# MySen_raspiGateway_EasyEDA_Schematic.net
KiCad netlist of a schematic drawn in EasyEDA
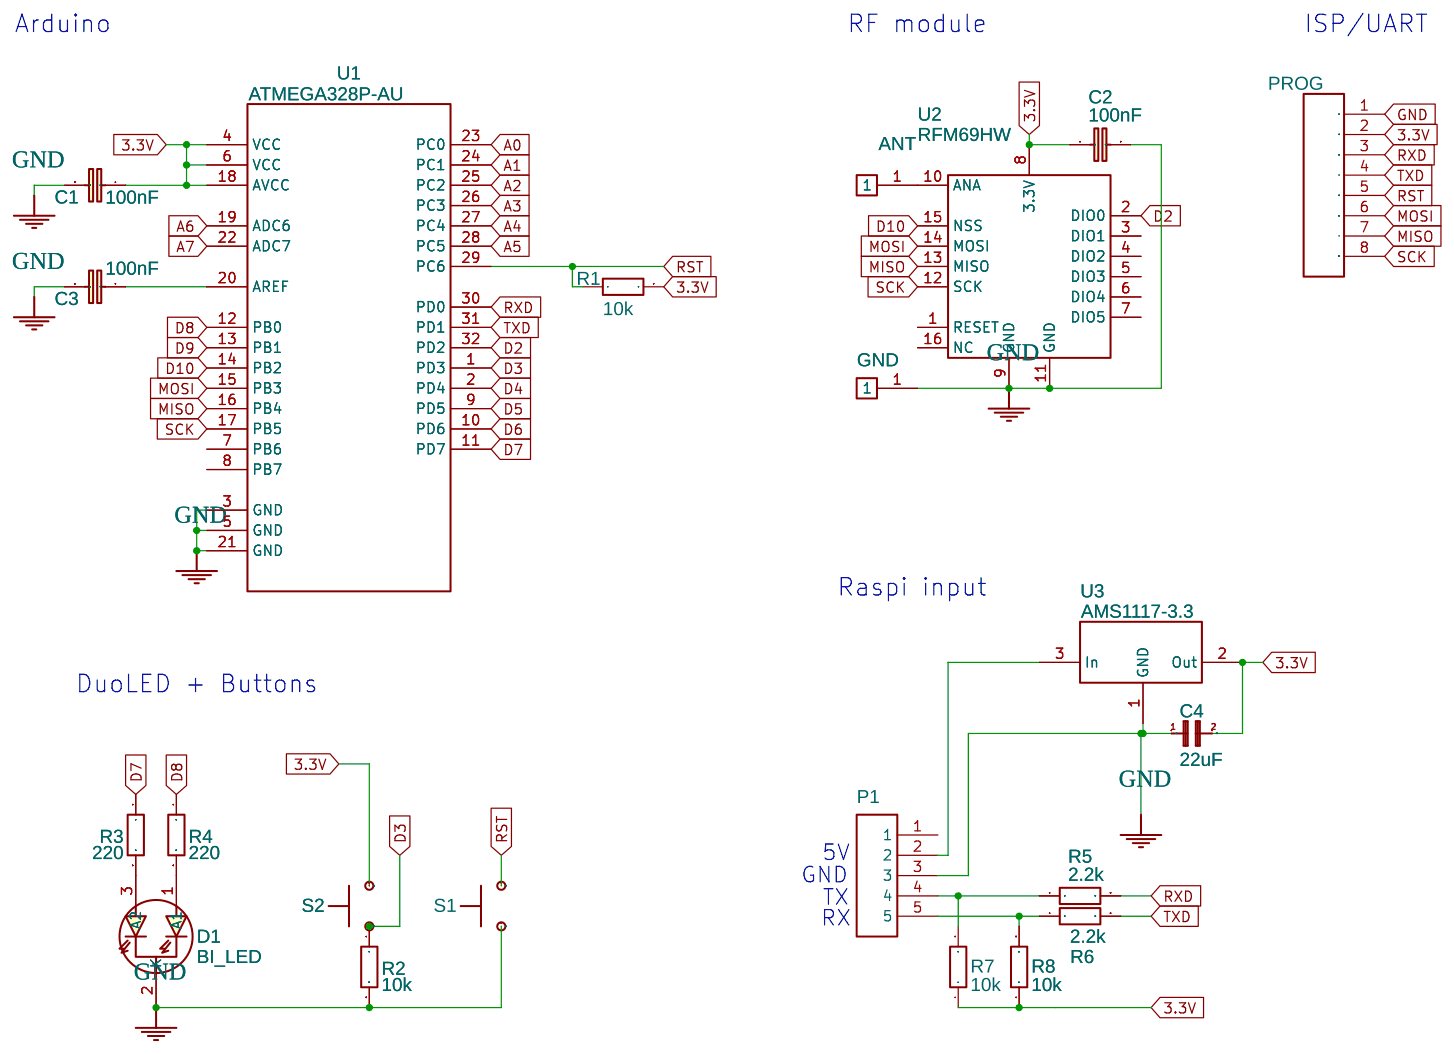
[diagram p0: schematic sheet]

(export (version "E")
  (design (tool "Eeschema 10.0.6"))
  (components
    (comp (ref "ANT") (value "1-S-PAD") (libsource (lib "") (part "Unknown_475_120")))
    (comp (ref "C1")
      (value "100nF")
      (fields (field (name "BOM_Manufacturer Part") "?"))
      (libsource (lib "") (part "Unknown_85_120"))
    )
    (comp (ref "C2")
      (value "100nF")
      (fields (field (name "BOM_Manufacturer Part") "?"))
      (libsource (lib "") (part "Unknown_590_100"))
    )
    (comp (ref "C3")
      (value "100nF")
      (fields (field (name "BOM_Manufacturer Part") "?"))
      (libsource (lib "") (part "Unknown_85_170"))
    )
    (comp (ref "C4")
      (value "22uF")
      (fields (field (name "BOM_Manufacturer Part") "?"))
      (libsource (lib "") (part "Unknown_630_390"))
    )
    (comp (ref "D1")
      (value "BI_LED")
      (fields (field (name "BOM_Manufacturer Part") "?"))
      (libsource (lib "") (part "Unknown_120_490"))
    )
    (comp (ref "GND") (value "1-S-PAD") (libsource (lib "") (part "Unknown_475_220")))
    (comp (ref "P1")
      (value "1x5 Header")
      (fields (field (name "BOM_Manufacturer Part") "?"))
      (libsource (lib "") (part "Unknown_485_480"))
    )
    (comp (ref "PROG")
      (value "Header 2pin")
      (fields (field (name "BOM_Manufacturer Part") "?"))
      (libsource (lib "") (part "Unknown_705_75"))
    )
    (comp (ref "R1")
      (value "10k")
      (fields (field (name "BOM_Manufacturer Part") "1206 J000T5E"))
      (libsource (lib "") (part "Unknown_350_170"))
    )
    (comp (ref "R2")
      (value "10k")
      (fields (field (name "BOM_Manufacturer Part") "1206 J000T5E"))
      (libsource (lib "") (part "Unknown_225_505"))
    )
    (comp (ref "R3")
      (value "220")
      (fields (field (name "BOM_Manufacturer Part") "1206 J000T5E"))
      (libsource (lib "") (part "Unknown_110_440"))
    )
    (comp (ref "R4")
      (value "220")
      (fields (field (name "BOM_Manufacturer Part") "1206 J000T5E"))
      (libsource (lib "") (part "Unknown_130_440"))
    )
    (comp (ref "R5")
      (value "2.2k")
      (fields (field (name "BOM_Manufacturer Part") "1206 J000T5E"))
      (libsource (lib "") (part "Unknown_575_470"))
    )
    (comp (ref "R6")
      (value "2.2k")
      (fields (field (name "BOM_Manufacturer Part") "1206 J000T5E"))
      (libsource (lib "") (part "Unknown_575_480"))
    )
    (comp (ref "R7")
      (value "10k")
      (fields (field (name "BOM_Manufacturer Part") "1206 J000T5E"))
      (libsource (lib "") (part "Unknown_515_505"))
    )
    (comp (ref "R8")
      (value "10k")
      (fields (field (name "BOM_Manufacturer Part") "1206 J000T5E"))
      (libsource (lib "") (part "Unknown_545_505"))
    )
    (comp (ref "S1") (value "Momentary Switch Open") (libsource (lib "") (part "Unknown_290_475")))
    (comp (ref "S2") (value "Momentary Switch Open") (libsource (lib "") (part "Unknown_225_475")))
    (comp (ref "U1") (value "ATMEGA328P-AU") (libsource (lib "") (part "Unknown_215_190")))
    (comp (ref "U2")
      (value "RFM69HW")
      (fields (field (name "BOM_Manufacturer Part") "?"))
      (libsource (lib "") (part "Unknown_550_135"))
    )
    (comp (ref "U3") (value "AMS1117-3.3") (libsource (lib "") (part "Unknown_605_355")))
  )
  (nets
    (net (code "1") (name "3.3V") (class "Default")
      (node (ref "C1") (pin "1") (pinfunction "1_1") (pintype "unspecified"))
      (node (ref "C2") (pin "1") (pinfunction "1_1") (pintype "unspecified"))
      (node (ref "C4") (pin "2") (pinfunction "2_2") (pintype "unspecified"))
      (node (ref "PROG") (pin "2") (pinfunction "2_2") (pintype "unspecified"))
      (node (ref "R1") (pin "2") (pinfunction "2_2") (pintype "input"))
      (node (ref "R7") (pin "1") (pinfunction "1_1") (pintype "input"))
      (node (ref "R8") (pin "1") (pinfunction "1_1") (pintype "input"))
      (node (ref "S2") (pin "3") (pinfunction "2_3") (pintype "unspecified"))
      (node (ref "U1") (pin "18") (pinfunction "AVCC_18") (pintype "passive"))
      (node (ref "U1") (pin "4") (pinfunction "VCC_4") (pintype "passive"))
      (node (ref "U1") (pin "6") (pinfunction "VCC_6") (pintype "passive"))
      (node (ref "U2") (pin "8") (pinfunction "3.3V_8") (pintype "passive"))
      (node (ref "U3") (pin "2") (pinfunction "Out_2") (pintype "unspecified"))
    )
    (net (code "2") (name "A0") (class "Default")
      (node (ref "U1") (pin "23") (pinfunction "PC0_23") (pintype "unspecified"))
    )
    (net (code "3") (name "A1") (class "Default")
      (node (ref "U1") (pin "24") (pinfunction "PC1_24") (pintype "unspecified"))
    )
    (net (code "4") (name "A2") (class "Default")
      (node (ref "U1") (pin "25") (pinfunction "PC2_25") (pintype "unspecified"))
    )
    (net (code "5") (name "A3") (class "Default")
      (node (ref "U1") (pin "26") (pinfunction "PC3_26") (pintype "unspecified"))
    )
    (net (code "6") (name "A4") (class "Default")
      (node (ref "U1") (pin "27") (pinfunction "PC4_27") (pintype "unspecified"))
    )
    (net (code "7") (name "A5") (class "Default")
      (node (ref "U1") (pin "28") (pinfunction "PC5_28") (pintype "unspecified"))
    )
    (net (code "8") (name "A6") (class "Default")
      (node (ref "U1") (pin "19") (pinfunction "ADC6_19") (pintype "input"))
    )
    (net (code "9") (name "A7") (class "Default")
      (node (ref "U1") (pin "22") (pinfunction "ADC7_22") (pintype "input"))
    )
    (net (code "10") (name "D2") (class "Default")
      (node (ref "U1") (pin "32") (pinfunction "PD2_32") (pintype "unspecified"))
      (node (ref "U2") (pin "2") (pinfunction "DIO0_2") (pintype "bidirectional"))
    )
    (net (code "11") (name "D3") (class "Default")
      (node (ref "R2") (pin "1") (pinfunction "1_1") (pintype "input"))
      (node (ref "S2") (pin "1") (pinfunction "1_1") (pintype "unspecified"))
      (node (ref "U1") (pin "1") (pinfunction "PD3_1") (pintype "unspecified"))
    )
    (net (code "12") (name "D4") (class "Default")
      (node (ref "U1") (pin "2") (pinfunction "PD4_2") (pintype "unspecified"))
    )
    (net (code "13") (name "D5") (class "Default")
      (node (ref "U1") (pin "9") (pinfunction "PD5_9") (pintype "unspecified"))
    )
    (net (code "14") (name "D6") (class "Default")
      (node (ref "U1") (pin "10") (pinfunction "PD6_10") (pintype "unspecified"))
    )
    (net (code "15") (name "D7") (class "Default")
      (node (ref "R3") (pin "1") (pinfunction "1_1") (pintype "input"))
      (node (ref "U1") (pin "11") (pinfunction "PD7_11") (pintype "unspecified"))
    )
    (net (code "16") (name "D8") (class "Default")
      (node (ref "R4") (pin "1") (pinfunction "1_1") (pintype "input"))
      (node (ref "U1") (pin "12") (pinfunction "PB0_12") (pintype "unspecified"))
    )
    (net (code "17") (name "D9") (class "Default")
      (node (ref "U1") (pin "13") (pinfunction "PB1_13") (pintype "unspecified"))
    )
    (net (code "18") (name "D10") (class "Default")
      (node (ref "U1") (pin "14") (pinfunction "PB2_14") (pintype "unspecified"))
      (node (ref "U2") (pin "15") (pinfunction "NSS_15") (pintype "input"))
    )
    (net (code "19") (name "GND") (class "Default")
      (node (ref "C1") (pin "2") (pinfunction "2_2") (pintype "unspecified"))
      (node (ref "C2") (pin "2") (pinfunction "2_2") (pintype "unspecified"))
      (node (ref "C3") (pin "2") (pinfunction "2_2") (pintype "unspecified"))
      (node (ref "C4") (pin "1") (pinfunction "1_1") (pintype "unspecified"))
      (node (ref "D1") (pin "2") (pinfunction "K_2") (pintype "input"))
      (node (ref "GND") (pin "1") (pinfunction "1_1") (pintype "unspecified"))
      (node (ref "P1") (pin "3") (pinfunction "3_3") (pintype "unspecified"))
      (node (ref "PROG") (pin "1") (pinfunction "1_1") (pintype "unspecified"))
      (node (ref "R2") (pin "2") (pinfunction "2_2") (pintype "input"))
      (node (ref "S1") (pin "1") (pinfunction "1_1") (pintype "unspecified"))
      (node (ref "U1") (pin "21") (pinfunction "GND_21") (pintype "unspecified"))
      (node (ref "U1") (pin "3") (pinfunction "GND_3") (pintype "unspecified"))
      (node (ref "U1") (pin "5") (pinfunction "GND_5") (pintype "unspecified"))
      (node (ref "U2") (pin "11") (pinfunction "GND_11") (pintype "passive"))
      (node (ref "U2") (pin "9") (pinfunction "GND_9") (pintype "passive"))
      (node (ref "U3") (pin "1") (pinfunction "GND_1") (pintype "unspecified"))
    )
    (net (code "20") (name "MISO") (class "Default")
      (node (ref "PROG") (pin "7") (pinfunction "7_7") (pintype "unspecified"))
      (node (ref "U1") (pin "16") (pinfunction "PB4_16") (pintype "unspecified"))
      (node (ref "U2") (pin "13") (pinfunction "MISO_13") (pintype "unspecified"))
    )
    (net (code "21") (name "MOSI") (class "Default")
      (node (ref "PROG") (pin "6") (pinfunction "6_6") (pintype "unspecified"))
      (node (ref "U1") (pin "15") (pinfunction "PB3_15") (pintype "unspecified"))
      (node (ref "U2") (pin "14") (pinfunction "MOSI_14") (pintype "input"))
    )
    (net (code "22") (name "Net-(D1-A1)") (class "Default")
      (node (ref "D1") (pin "1") (pinfunction "A1_1") (pintype "input"))
      (node (ref "R4") (pin "2") (pinfunction "2_2") (pintype "input"))
    )
    (net (code "23") (name "Net-(D1-A2)") (class "Default")
      (node (ref "D1") (pin "3") (pinfunction "A2_3") (pintype "input"))
      (node (ref "R3") (pin "2") (pinfunction "2_2") (pintype "input"))
    )
    (net (code "24") (name "Net-(P1-Pad4)") (class "Default")
      (node (ref "P1") (pin "4") (pinfunction "4_4") (pintype "unspecified"))
      (node (ref "R5") (pin "1") (pinfunction "1_1") (pintype "input"))
      (node (ref "R7") (pin "2") (pinfunction "2_2") (pintype "input"))
    )
    (net (code "25") (name "Net-(P1-Pad5)") (class "Default")
      (node (ref "P1") (pin "5") (pinfunction "5_5") (pintype "unspecified"))
      (node (ref "R6") (pin "1") (pinfunction "1_1") (pintype "input"))
      (node (ref "R8") (pin "2") (pinfunction "2_2") (pintype "input"))
    )
    (net (code "26") (name "Net-(U1-AREF)") (class "Default")
      (node (ref "C3") (pin "1") (pinfunction "1_1") (pintype "unspecified"))
      (node (ref "U1") (pin "20") (pinfunction "AREF_20") (pintype "input"))
    )
    (net (code "27") (name "Net-(U2-ANA)") (class "Default")
      (node (ref "ANT") (pin "1") (pinfunction "1_1") (pintype "unspecified"))
      (node (ref "U2") (pin "10") (pinfunction "ANA_10") (pintype "unspecified"))
    )
    (net (code "28") (name "Net-(U3-In)") (class "Default")
      (node (ref "P1") (pin "2") (pinfunction "2_2") (pintype "unspecified"))
      (node (ref "U3") (pin "3") (pinfunction "In_3") (pintype "unspecified"))
    )
    (net (code "29") (name "RST") (class "Default")
      (node (ref "PROG") (pin "5") (pinfunction "5_5") (pintype "unspecified"))
      (node (ref "R1") (pin "1") (pinfunction "1_1") (pintype "input"))
      (node (ref "S1") (pin "3") (pinfunction "2_3") (pintype "unspecified"))
      (node (ref "U1") (pin "29") (pinfunction "PC6_29") (pintype "unspecified"))
    )
    (net (code "30") (name "RXD") (class "Default")
      (node (ref "PROG") (pin "3") (pinfunction "3_3") (pintype "unspecified"))
      (node (ref "R5") (pin "2") (pinfunction "2_2") (pintype "input"))
      (node (ref "U1") (pin "30") (pinfunction "PD0_30") (pintype "unspecified"))
    )
    (net (code "31") (name "SCK") (class "Default")
      (node (ref "PROG") (pin "8") (pinfunction "8_8") (pintype "unspecified"))
      (node (ref "U1") (pin "17") (pinfunction "PB5_17") (pintype "unspecified"))
      (node (ref "U2") (pin "12") (pinfunction "SCK_12") (pintype "input"))
    )
    (net (code "32") (name "TXD") (class "Default")
      (node (ref "PROG") (pin "4") (pinfunction "4_4") (pintype "unspecified"))
      (node (ref "R6") (pin "2") (pinfunction "2_2") (pintype "input"))
      (node (ref "U1") (pin "31") (pinfunction "PD1_31") (pintype "unspecified"))
    )
    (net (code "33") (name "unconnected-(P1-Pad1)") (class "Default")
      (node (ref "P1") (pin "1") (pinfunction "1_1") (pintype "unspecified"))
    )
    (net (code "34") (name "unconnected-(U1-PB6-Pad7)") (class "Default")
      (node (ref "U1") (pin "7") (pinfunction "PB6_7") (pintype "unspecified"))
    )
    (net (code "35") (name "unconnected-(U1-PB7-Pad8)") (class "Default")
      (node (ref "U1") (pin "8") (pinfunction "PB7_8") (pintype "unspecified"))
    )
    (net (code "36") (name "unconnected-(U2-DIO1-Pad3)") (class "Default")
      (node (ref "U2") (pin "3") (pinfunction "DIO1_3") (pintype "bidirectional"))
    )
    (net (code "37") (name "unconnected-(U2-DIO2-Pad4)") (class "Default")
      (node (ref "U2") (pin "4") (pinfunction "DIO2_4") (pintype "bidirectional"))
    )
    (net (code "38") (name "unconnected-(U2-DIO3-Pad5)") (class "Default")
      (node (ref "U2") (pin "5") (pinfunction "DIO3_5") (pintype "bidirectional"))
    )
    (net (code "39") (name "unconnected-(U2-DIO4-Pad6)") (class "Default")
      (node (ref "U2") (pin "6") (pinfunction "DIO4_6") (pintype "bidirectional"))
    )
    (net (code "40") (name "unconnected-(U2-DIO5-Pad7)") (class "Default")
      (node (ref "U2") (pin "7") (pinfunction "DIO5_7") (pintype "bidirectional"))
    )
    (net (code "41") (name "unconnected-(U2-NC-Pad16)") (class "Default")
      (node (ref "U2") (pin "16") (pinfunction "NC_16") (pintype "unspecified"))
    )
    (net (code "42") (name "unconnected-(U2-RESET-Pad1)") (class "Default")
      (node (ref "U2") (pin "1") (pinfunction "RESET_1") (pintype "bidirectional"))
    )
  )
)
